# LVBMSBQF_schematic.net
KiCad netlist of a schematic drawn in Altium Designer
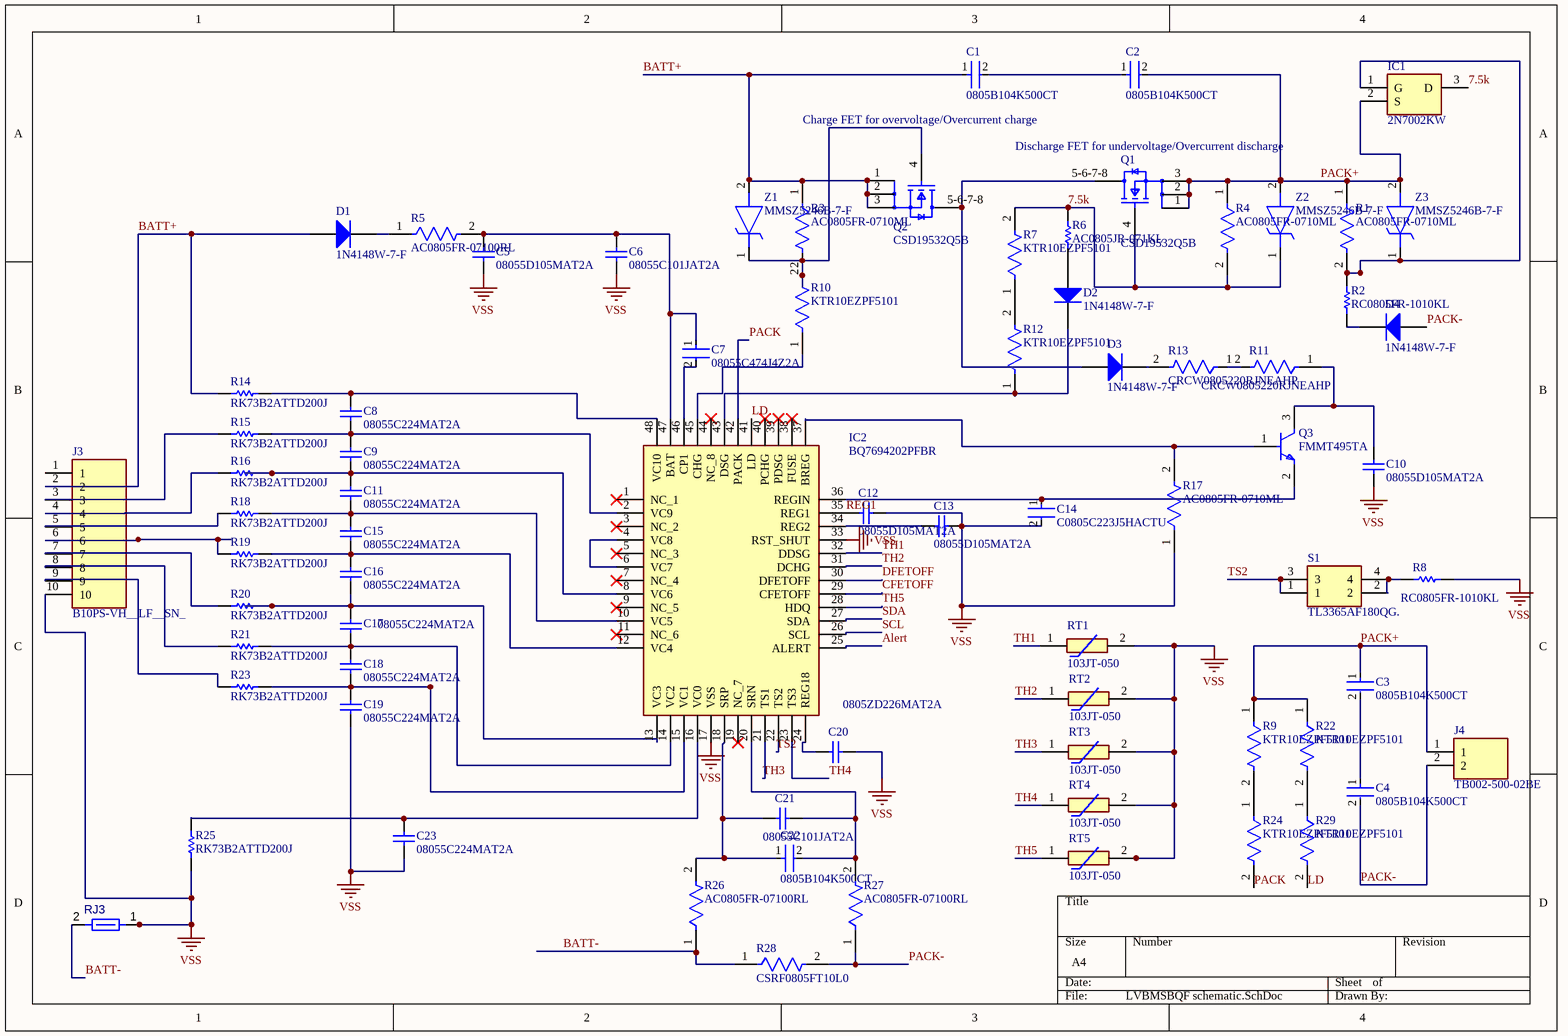
[diagram p0: LVBMSBQF schematic.SchDoc]

(export (version "E")
  (design (tool "Eeschema 10.0.6"))
  (components
    (comp (ref "C1")
      (value "0805B104K500CT")
      (footprint "FP-0805B-IPC_C")
      (description "CAP CER 0.1UF 50V X7R 0805")
      (fields (field (name "VOLTAGE") "50V") (field (name "TOLERANCE") "10%"))
      (libsource (lib "Altium Content Vault") (part "02cd4be3c70576c341d710602a673aa"))
    )
    (comp (ref "C2")
      (value "0805B104K500CT")
      (footprint "FP-0805B-IPC_C")
      (description "CAP CER 0.1UF 50V X7R 0805")
      (fields (field (name "VOLTAGE") "50V") (field (name "TOLERANCE") "10%"))
      (libsource (lib "Altium Content Vault") (part "02cd4be3c70576c341d710602a673aa"))
    )
    (comp (ref "C3")
      (value "0805B104K500CT")
      (footprint "FP-0805B-IPC_C")
      (description "CAP CER 0.1UF 50V X7R 0805")
      (fields (field (name "VOLTAGE") "50V") (field (name "TOLERANCE") "10%"))
      (libsource (lib "Altium Content Vault") (part "02cd4be3c70576c341d710602a673aa"))
    )
    (comp (ref "C4")
      (value "0805B104K500CT")
      (footprint "FP-0805B-IPC_C")
      (description "CAP CER 0.1UF 50V X7R 0805")
      (fields (field (name "VOLTAGE") "50V") (field (name "TOLERANCE") "10%"))
      (libsource (lib "Altium Content Vault") (part "02cd4be3c70576c341d710602a673aa"))
    )
    (comp (ref "C5")
      (value "08055D105MAT2A")
      (footprint "CAPC2013X152X50ML20T25")
      (libsource (lib "Altium Content Vault") (part "CAP"))
    )
    (comp (ref "C6")
      (value "08055C101JAT2A")
      (footprint "CAPC2013X94X50NL20T25")
      (libsource (lib "Altium Content Vault") (part "CAP"))
    )
    (comp (ref "C7")
      (value "08055C474J4Z2A")
      (footprint "FP-0805-L_2_01_0_2-W_1_25-IPC_B")
      (description "Automotive Ceramic Capacitor, 0805, 470nF, 5%, X7R, 15%, 50V")
      (fields (field (name "TOLERANCE") "5%"))
      (libsource (lib "Altium Content Vault") (part "b4654b650e69147ec39a6b967a45e02"))
    )
    (comp (ref "C8")
      (value "08055C224MAT2A")
      (footprint "CAPC2013X140X50NL20T25")
      (libsource (lib "Altium Content Vault") (part "CAP"))
    )
    (comp (ref "C9")
      (value "08055C224MAT2A")
      (footprint "CAPC2013X140X50NL20T25")
      (libsource (lib "Altium Content Vault") (part "CAP"))
    )
    (comp (ref "C10")
      (value "08055D105MAT2A")
      (footprint "CAPC2013X152X50ML20T25")
      (libsource (lib "Altium Content Vault") (part "CAP"))
    )
    (comp (ref "C11")
      (value "08055C224MAT2A")
      (footprint "CAPC2013X140X50NL20T25")
      (libsource (lib "Altium Content Vault") (part "CAP"))
    )
    (comp (ref "C12")
      (value "08055D105MAT2A")
      (footprint "CAPC2013X152X50ML20T25")
      (libsource (lib "Altium Content Vault") (part "CAP"))
    )
    (comp (ref "C13")
      (value "08055D105MAT2A")
      (footprint "CAPC2013X152X50ML20T25")
      (libsource (lib "Altium Content Vault") (part "CAP"))
    )
    (comp (ref "C14")
      (value "C0805C223J5HACTU")
      (footprint "FP-C0805C-DN-MFG")
      (description "CAP CER 0.022UF 50V X8R 0805")
      (fields
        (field (name "TOLERANCE") "0.05")
        (field (name "OCTOPART") "https://octopart.com/c0805c223j5hactu-kemet-18638969")
      )
      (libsource (lib "Altium Content Vault") (part "b4654b650e69147ec39a6b967a45e02"))
    )
    (comp (ref "C15")
      (value "08055C224MAT2A")
      (footprint "CAPC2013X140X50NL20T25")
      (libsource (lib "Altium Content Vault") (part "CAP"))
    )
    (comp (ref "C16")
      (value "08055C224MAT2A")
      (footprint "CAPC2013X140X50NL20T25")
      (libsource (lib "Altium Content Vault") (part "CAP"))
    )
    (comp (ref "C17")
      (value "08055C224MAT2A")
      (footprint "CAPC2013X140X50NL20T25")
      (libsource (lib "Altium Content Vault") (part "CAP"))
    )
    (comp (ref "C18")
      (value "08055C224MAT2A")
      (footprint "CAPC2013X140X50NL20T25")
      (libsource (lib "Altium Content Vault") (part "CAP"))
    )
    (comp (ref "C19")
      (value "08055C224MAT2A")
      (footprint "CAPC2013X140X50NL20T25")
      (libsource (lib "Altium Content Vault") (part "CAP"))
    )
    (comp (ref "C20")
      (value "0805ZD226MAT2A")
      (footprint "CAPC2013X152X50ML20T25")
      (libsource (lib "Altium Content Vault") (part "CAP"))
    )
    (comp (ref "C21")
      (value "08055C101JAT2A")
      (footprint "CAPC2013X94X50NL20T25")
      (libsource (lib "Altium Content Vault") (part "CAP"))
    )
    (comp (ref "C22")
      (value "0805B104K500CT")
      (footprint "FP-0805B-IPC_C")
      (description "CAP CER 0.1UF 50V X7R 0805")
      (fields (field (name "VOLTAGE") "50V") (field (name "TOLERANCE") "10%"))
      (libsource (lib "Altium Content Vault") (part "02cd4be3c70576c341d710602a673aa"))
    )
    (comp (ref "C23")
      (value "08055C224MAT2A")
      (footprint "CAPC2013X140X50NL20T25")
      (libsource (lib "Altium Content Vault") (part "CAP"))
    )
    (comp (ref "D1")
      (value "1N4148W-7-F")
      (footprint "DIOD-SOD123-2_V")
      (description "Fast Switching Diode, 100 V, 0.15 A, -65 to 150 degC, 2-Pin?SOD123, RoHS, Tape and Reel")
      (libsource (lib "Altium Content Vault") (part "D-AK-2"))
    )
    (comp (ref "D2")
      (value "1N4148W-7-F")
      (footprint "DIOD-SOD123-2_V")
      (description "Fast Switching Diode, 100 V, 0.15 A, -65 to 150 degC, 2-Pin?SOD123, RoHS, Tape and Reel")
      (libsource (lib "Altium Content Vault") (part "D-AK-2"))
    )
    (comp (ref "D3")
      (value "1N4148W-7-F")
      (footprint "DIOD-SOD123-2_V")
      (description "Fast Switching Diode, 100 V, 0.15 A, -65 to 150 degC, 2-Pin?SOD123, RoHS, Tape and Reel")
      (libsource (lib "Altium Content Vault") (part "D-AK-2"))
    )
    (comp (ref "D4")
      (value "1N4148W-7-F")
      (footprint "DIOD-SOD123-2_V")
      (description "Fast Switching Diode, 100 V, 0.15 A, -65 to 150 degC, 2-Pin?SOD123, RoHS, Tape and Reel")
      (fields (field (name "MANUFACTURER") "DiodesIncorporated"))
      (libsource (lib "Altium Content Vault") (part "D-AK-2"))
    )
    (comp (ref "IC1")
      (value "2N7002KW")
      (footprint "SamacSys:SOT65P210X110-3N")
      (description "Integrated Circuit")
      (fields (field (name "MOUSER PART NUMBER") "512-2N7002KW"))
      (libsource (lib "*") (part "2N7002KW"))
    )
    (comp (ref "IC2")
      (value "BQ7694202PFBR")
      (footprint "SamacSys:QFP50P900X900X120-48N")
      (description "Integrated Circuit")
      (fields (field (name "MOUSER PART NUMBER") "595-BQ7694202PFBR"))
      (libsource (lib "*") (part "BQ7694202PFBR"))
    )
    (comp (ref "J3")
      (value "B10PS-VH__LF__SN_")
      (footprint "SamacSys:B10PSVHLFSN")
      (description "Connector")
      (fields (field (name "MANUFACTURER_PART_NUMBER") "B10PS-VH (LF)(SN)"))
      (libsource (lib "*") (part "B10PS-VH__LF__SN_"))
    )
    (comp (ref "J4")
      (value "TB002-500-02BE")
      (footprint "SamacSys:TB00250002BE")
      (description "Connector")
      (fields (field (name "MOUSER PART NUMBER") "490-TB002-500-02BE"))
      (libsource (lib "*") (part "TB002-500-02BE"))
    )
    (comp (ref "Q1")
      (value "CSD19532Q5B")
      (footprint "FP-DNK0008A-MFG")
      (description "MOSFET N-CH 100V 100A 8SON")
      (fields (field (name "OCTOPART") "https://octopart.com/csd19532q5b-texas+instruments-32890191"))
      (libsource (lib "Altium Content Vault") (part "6fb2c024a3b9031f6d89538bc87a0fd"))
    )
    (comp (ref "Q2")
      (value "CSD19532Q5B")
      (footprint "FP-DNK0008A-MFG")
      (description "MOSFET N-CH 100V 100A 8SON")
      (fields (field (name "OCTOPART") "https://octopart.com/csd19532q5b-texas+instruments-32890191"))
      (libsource (lib "Altium Content Vault") (part "6fb2c024a3b9031f6d89538bc87a0fd"))
    )
    (comp (ref "Q3")
      (value "FMMT495TA")
      (footprint "FP-SOT23-MFG")
      (description "TRANS NPN 150V 1A SOT23-3")
      (fields (field (name "OCTOPART") "https://octopart.com/fmmt495ta-diodes+inc.-356348"))
      (libsource (lib "Altium Content Vault") (part "b44e953556f554d0102664c7d152cb4"))
    )
    (comp (ref "R1")
      (value "AC0805FR-0710ML")
      (footprint "FP-AC0805-MFG")
      (description "RES SMD 10M OHM 1% 1/8W 0805")
      (fields
        (field (name "TOLERANCE") "0.01")
        (field (name "OCTOPART") "https://octopart.com/ac0805fr-0710ml-yageo-71367525")
      )
      (libsource (lib "Altium Content Vault") (part "1029c3af85768c4190bb7ad29bc67b5"))
    )
    (comp (ref "R2")
      (value "RC0805FR-1010KL")
      (footprint "RESC2013X60X35LL10T20")
      (libsource (lib "Altium Content Vault") (part "RES"))
    )
    (comp (ref "R3")
      (value "AC0805FR-0710ML")
      (footprint "FP-AC0805-MFG")
      (description "RES SMD 10M OHM 1% 1/8W 0805")
      (fields
        (field (name "TOLERANCE") "0.01")
        (field (name "OCTOPART") "https://octopart.com/ac0805fr-0710ml-yageo-71367525")
      )
      (libsource (lib "Altium Content Vault") (part "1029c3af85768c4190bb7ad29bc67b5"))
    )
    (comp (ref "R4")
      (value "AC0805FR-0710ML")
      (footprint "FP-AC0805-MFG")
      (description "RES SMD 10M OHM 1% 1/8W 0805")
      (fields
        (field (name "TOLERANCE") "0.01")
        (field (name "OCTOPART") "https://octopart.com/ac0805fr-0710ml-yageo-71367525")
      )
      (libsource (lib "Altium Content Vault") (part "1029c3af85768c4190bb7ad29bc67b5"))
    )
    (comp (ref "R5")
      (value "AC0805FR-07100RL")
      (footprint "FP-AC0805-MFG")
      (description "Res Thick Film 0805 100 Ohm 1% 1/8W ±100ppm/°C Molded SMD Paper T/R")
      (fields
        (field (name "TOLERANCE") "0.01")
        (field (name "OCTOPART") "https://octopart.com/ac0805fr-07100rl-yageo-24517276")
      )
      (libsource (lib "Altium Content Vault") (part "1029c3af85768c4190bb7ad29bc67b5"))
    )
    (comp (ref "R6")
      (value "AC0805JR-071KL")
      (footprint "RESC2013X60X35LL10T20")
      (libsource (lib "Altium Content Vault") (part "RES"))
    )
    (comp (ref "R7")
      (value "KTR10EZPF5101")
      (footprint "FP-KTR10-MFG")
      (description "Res Thick Film 0805 5.1kΩ 1% 0.125W ±100ppm/°C Automotive Paper T/R")
      (fields (field (name "TOLERANCE") "1%"))
      (libsource (lib "Altium Content Vault") (part "1029c3af85768c4190bb7ad29bc67b5"))
    )
    (comp (ref "R8")
      (value "RC0805FR-1010KL")
      (footprint "RESC2013X60X35LL10T20")
      (libsource (lib "Altium Content Vault") (part "RES"))
    )
    (comp (ref "R9")
      (value "KTR10EZPF5101")
      (footprint "FP-KTR10-MFG")
      (description "Res Thick Film 0805 5.1kΩ 1% 0.125W ±100ppm/°C Automotive Paper T/R")
      (fields (field (name "TOLERANCE") "1%"))
      (libsource (lib "Altium Content Vault") (part "1029c3af85768c4190bb7ad29bc67b5"))
    )
    (comp (ref "R10")
      (value "KTR10EZPF5101")
      (footprint "FP-KTR10-MFG")
      (description "Res Thick Film 0805 5.1kΩ 1% 0.125W ±100ppm/°C Automotive Paper T/R")
      (fields (field (name "TOLERANCE") "1%"))
      (libsource (lib "Altium Content Vault") (part "1029c3af85768c4190bb7ad29bc67b5"))
    )
    (comp (ref "R11")
      (value "CRCW0805220RJNEAHP")
      (footprint "FP-CRCW0805-HPe3-IPC_A")
      (description "RES Thick Film, 220Ω, 5%, 0.5W, 200ppm/°C, 0805")
      (fields (field (name "TOLERANCE") "5%"))
      (libsource (lib "Altium Content Vault") (part "1029c3af85768c4190bb7ad29bc67b5"))
    )
    (comp (ref "R12")
      (value "KTR10EZPF5101")
      (footprint "FP-KTR10-MFG")
      (description "Res Thick Film 0805 5.1kΩ 1% 0.125W ±100ppm/°C Automotive Paper T/R")
      (fields (field (name "TOLERANCE") "1%"))
      (libsource (lib "Altium Content Vault") (part "1029c3af85768c4190bb7ad29bc67b5"))
    )
    (comp (ref "R13")
      (value "CRCW0805220RJNEAHP")
      (footprint "FP-CRCW0805-HPe3-IPC_A")
      (description "RES Thick Film, 220Ω, 5%, 0.5W, 200ppm/°C, 0805")
      (fields (field (name "TOLERANCE") "5%"))
      (libsource (lib "Altium Content Vault") (part "1029c3af85768c4190bb7ad29bc67b5"))
    )
    (comp (ref "R14")
      (value "RK73B2ATTD200J")
      (footprint "RESC2013X60X30ML20T20")
      (libsource (lib "Altium Content Vault") (part "RES"))
    )
    (comp (ref "R15")
      (value "RK73B2ATTD200J")
      (footprint "RESC2013X60X30ML20T20")
      (libsource (lib "Altium Content Vault") (part "RES"))
    )
    (comp (ref "R16")
      (value "RK73B2ATTD200J")
      (footprint "RESC2013X60X30ML20T20")
      (libsource (lib "Altium Content Vault") (part "RES"))
    )
    (comp (ref "R17")
      (value "AC0805FR-0710ML")
      (footprint "FP-AC0805-MFG")
      (description "RES SMD 10M OHM 1% 1/8W 0805")
      (fields
        (field (name "TOLERANCE") "0.01")
        (field (name "OCTOPART") "https://octopart.com/ac0805fr-0710ml-yageo-71367525")
      )
      (libsource (lib "Altium Content Vault") (part "1029c3af85768c4190bb7ad29bc67b5"))
    )
    (comp (ref "R18")
      (value "RK73B2ATTD200J")
      (footprint "RESC2013X60X30ML20T20")
      (libsource (lib "Altium Content Vault") (part "RES"))
    )
    (comp (ref "R19")
      (value "RK73B2ATTD200J")
      (footprint "RESC2013X60X30ML20T20")
      (libsource (lib "Altium Content Vault") (part "RES"))
    )
    (comp (ref "R20")
      (value "RK73B2ATTD200J")
      (footprint "RESC2013X60X30ML20T20")
      (libsource (lib "Altium Content Vault") (part "RES"))
    )
    (comp (ref "R21")
      (value "RK73B2ATTD200J")
      (footprint "RESC2013X60X30ML20T20")
      (libsource (lib "Altium Content Vault") (part "RES"))
    )
    (comp (ref "R22")
      (value "KTR10EZPF5101")
      (footprint "FP-KTR10-MFG")
      (description "Res Thick Film 0805 5.1kΩ 1% 0.125W ±100ppm/°C Automotive Paper T/R")
      (fields (field (name "TOLERANCE") "1%"))
      (libsource (lib "Altium Content Vault") (part "1029c3af85768c4190bb7ad29bc67b5"))
    )
    (comp (ref "R23")
      (value "RK73B2ATTD200J")
      (footprint "RESC2013X60X30ML20T20")
      (libsource (lib "Altium Content Vault") (part "RES"))
    )
    (comp (ref "R24")
      (value "KTR10EZPF5101")
      (footprint "FP-KTR10-MFG")
      (description "Res Thick Film 0805 5.1kΩ 1% 0.125W ±100ppm/°C Automotive Paper T/R")
      (fields (field (name "TOLERANCE") "1%"))
      (libsource (lib "Altium Content Vault") (part "1029c3af85768c4190bb7ad29bc67b5"))
    )
    (comp (ref "R25")
      (value "RK73B2ATTD200J")
      (footprint "RESC2013X60X30ML20T20")
      (libsource (lib "Altium Content Vault") (part "RES"))
    )
    (comp (ref "R26")
      (value "AC0805FR-07100RL")
      (footprint "FP-AC0805-MFG")
      (description "Res Thick Film 0805 100 Ohm 1% 1/8W ±100ppm/°C Molded SMD Paper T/R")
      (fields
        (field (name "TOLERANCE") "0.01")
        (field (name "OCTOPART") "https://octopart.com/ac0805fr-07100rl-yageo-24517276")
      )
      (libsource (lib "Altium Content Vault") (part "1029c3af85768c4190bb7ad29bc67b5"))
    )
    (comp (ref "R27")
      (value "AC0805FR-07100RL")
      (footprint "FP-AC0805-MFG")
      (description "Res Thick Film 0805 100 Ohm 1% 1/8W ±100ppm/°C Molded SMD Paper T/R")
      (fields
        (field (name "TOLERANCE") "0.01")
        (field (name "OCTOPART") "https://octopart.com/ac0805fr-07100rl-yageo-24517276")
      )
      (libsource (lib "Altium Content Vault") (part "1029c3af85768c4190bb7ad29bc67b5"))
    )
    (comp (ref "R28")
      (value "CSRF0805FT10L0")
      (footprint "FP-CSRF0805-IPC_A")
      (description "Foil on Ceramic Current Sensing Chip Resistor 10 mΩ ±1% 0.5W 0805 AEC Qualified")
      (fields (field (name "TOLERANCE") "1%"))
      (libsource (lib "Altium Content Vault") (part "1029c3af85768c4190bb7ad29bc67b5"))
    )
    (comp (ref "R29")
      (value "KTR10EZPF5101")
      (footprint "FP-KTR10-MFG")
      (description "Res Thick Film 0805 5.1kΩ 1% 0.125W ±100ppm/°C Automotive Paper T/R")
      (fields (field (name "TOLERANCE") "1%"))
      (libsource (lib "Altium Content Vault") (part "1029c3af85768c4190bb7ad29bc67b5"))
    )
    (comp (ref "RJ3")
      (value "Net Tie 0.6x1.4mm")
      (footprint "SHORT10_8MIL-FP")
      (libsource (lib "Toronto Met Formula Racing") (part "CMP-00022-00002-2"))
    )
    (comp (ref "RT1")
      (value "103JT-050")
      (footprint "SamacSys:103JT050")
      (description "Thermistor")
      (fields (field (name "MOUSER PART NUMBER") "954-103JT-050"))
      (libsource (lib "*") (part "103JT-050"))
    )
    (comp (ref "RT2")
      (value "103JT-050")
      (footprint "SamacSys:103JT050")
      (description "Thermistor")
      (fields (field (name "MOUSER PART NUMBER") "954-103JT-050"))
      (libsource (lib "*") (part "103JT-050"))
    )
    (comp (ref "RT3")
      (value "103JT-050")
      (footprint "SamacSys:103JT050")
      (description "Thermistor")
      (fields (field (name "MOUSER PART NUMBER") "954-103JT-050"))
      (libsource (lib "*") (part "103JT-050"))
    )
    (comp (ref "RT4")
      (value "103JT-050")
      (footprint "SamacSys:103JT050")
      (description "Thermistor")
      (fields (field (name "MOUSER PART NUMBER") "954-103JT-050"))
      (libsource (lib "*") (part "103JT-050"))
    )
    (comp (ref "RT5")
      (value "103JT-050")
      (footprint "SamacSys:103JT050")
      (description "Thermistor")
      (fields (field (name "MOUSER PART NUMBER") "954-103JT-050"))
      (libsource (lib "*") (part "103JT-050"))
    )
    (comp (ref "S1")
      (value "TL3365AF180QG.")
      (footprint "SamacSys:TL3365AF180QG")
      (description "Switch")
      (libsource (lib "*") (part "TL3365AF180QG."))
    )
    (comp (ref "Z1")
      (value "MMSZ5246B-7-F")
      (footprint "SamacSys:SOD3716X145N")
      (description "Zener Diode")
      (fields (field (name "MOUSER PART NUMBER") "621-MMSZ5246B-F"))
      (libsource (lib "*") (part "MMSZ5246B-7-F"))
    )
    (comp (ref "Z2")
      (value "MMSZ5246B-7-F")
      (footprint "SamacSys:SOD3716X145N")
      (description "Zener Diode")
      (fields (field (name "MOUSER PART NUMBER") "621-MMSZ5246B-F"))
      (libsource (lib "*") (part "MMSZ5246B-7-F"))
    )
    (comp (ref "Z3")
      (value "MMSZ5246B-7-F")
      (footprint "SamacSys:SOD3716X145N")
      (description "Zener Diode")
      (fields (field (name "MOUSER PART NUMBER") "621-MMSZ5246B-F"))
      (libsource (lib "*") (part "MMSZ5246B-7-F"))
    )
  )
  (nets
    (net (code "1") (name "/7.5k") (class "Default")
      (node (ref "IC1") (pin "3") (pinfunction "D_3") (pintype "passive"))
      (node (ref "Q1") (pin "4") (pinfunction "G_4") (pintype "passive"))
      (node (ref "R4") (pin "2") (pinfunction "2_2") (pintype "passive"))
      (node (ref "R6") (pin "2") (pinfunction "2_2") (pintype "passive"))
      (node (ref "R7") (pin "2") (pinfunction "2_2") (pintype "passive"))
      (node (ref "Z2") (pin "1") (pinfunction "K_1") (pintype "passive"))
    )
    (net (code "2") (name "/Alert") (class "Default")
      (node (ref "IC2") (pin "25") (pinfunction "ALERT_25") (pintype "passive"))
    )
    (net (code "3") (name "/BATT+") (class "Default")
      (node (ref "C1") (pin "1") (pinfunction "1_1") (pintype "passive"))
      (node (ref "D1") (pin "1") (pinfunction "A_1") (pintype "passive"))
      (node (ref "J3") (pin "2") (pinfunction "2_2") (pintype "passive"))
      (node (ref "Q2") (pin "1") (pinfunction "S_1") (pintype "passive"))
      (node (ref "Q2") (pin "2") (pinfunction "S_2") (pintype "passive"))
      (node (ref "Q2") (pin "3") (pinfunction "S_3") (pintype "passive"))
      (node (ref "R14") (pin "1") (pinfunction "1_1") (pintype "passive"))
      (node (ref "R3") (pin "1") (pinfunction "1_1") (pintype "passive"))
      (node (ref "Z1") (pin "2") (pinfunction "A_2") (pintype "passive"))
    )
    (net (code "4") (name "/BATT-") (class "Default")
      (node (ref "R26") (pin "1") (pinfunction "1_1") (pintype "passive"))
      (node (ref "R28") (pin "1") (pinfunction "1_1") (pintype "passive"))
      (node (ref "RJ3") (pin "2") (pinfunction "2_2") (pintype "passive"))
    )
    (net (code "5") (name "/CFETOFF") (class "Default")
      (node (ref "IC2") (pin "29") (pinfunction "CFETOFF_29") (pintype "passive"))
    )
    (net (code "6") (name "/DFETOFF") (class "Default")
      (node (ref "IC2") (pin "30") (pinfunction "DFETOFF_30") (pintype "passive"))
    )
    (net (code "7") (name "/LD") (class "Default")
      (node (ref "IC2") (pin "41") (pinfunction "LD_41") (pintype "passive"))
      (node (ref "R29") (pin "2") (pinfunction "2_2") (pintype "passive"))
    )
    (net (code "8") (name "/PACK") (class "Default")
      (node (ref "IC2") (pin "42") (pinfunction "PACK_42") (pintype "passive"))
      (node (ref "R24") (pin "2") (pinfunction "2_2") (pintype "passive"))
    )
    (net (code "9") (name "/PACK+") (class "Default")
      (node (ref "C2") (pin "2") (pinfunction "2_2") (pintype "passive"))
      (node (ref "C3") (pin "1") (pinfunction "1_1") (pintype "passive"))
      (node (ref "IC1") (pin "2") (pinfunction "S_2") (pintype "passive"))
      (node (ref "J4") (pin "1") (pinfunction "1_1") (pintype "passive"))
      (node (ref "Q1") (pin "1") (pinfunction "S_1") (pintype "passive"))
      (node (ref "Q1") (pin "2") (pinfunction "S_2") (pintype "passive"))
      (node (ref "Q1") (pin "3") (pinfunction "S_3") (pintype "passive"))
      (node (ref "R1") (pin "1") (pinfunction "1_1") (pintype "passive"))
      (node (ref "R22") (pin "1") (pinfunction "1_1") (pintype "passive"))
      (node (ref "R4") (pin "1") (pinfunction "1_1") (pintype "passive"))
      (node (ref "R9") (pin "1") (pinfunction "1_1") (pintype "passive"))
      (node (ref "Z2") (pin "2") (pinfunction "A_2") (pintype "passive"))
      (node (ref "Z3") (pin "2") (pinfunction "A_2") (pintype "passive"))
    )
    (net (code "10") (name "/PACK-") (class "Default")
      (node (ref "C4") (pin "2") (pinfunction "2_2") (pintype "passive"))
      (node (ref "D4") (pin "1") (pinfunction "A_1") (pintype "passive"))
      (node (ref "J4") (pin "2") (pinfunction "2_2") (pintype "passive"))
      (node (ref "R27") (pin "1") (pinfunction "1_1") (pintype "passive"))
      (node (ref "R28") (pin "2") (pinfunction "2_2") (pintype "passive"))
    )
    (net (code "11") (name "/REG1") (class "Default")
      (node (ref "C12") (pin "1") (pinfunction "1_1") (pintype "passive"))
      (node (ref "IC2") (pin "35") (pinfunction "REG1_35") (pintype "passive"))
    )
    (net (code "12") (name "/SCL") (class "Default")
      (node (ref "IC2") (pin "26") (pinfunction "SCL_26") (pintype "passive"))
    )
    (net (code "13") (name "/SDA") (class "Default")
      (node (ref "IC2") (pin "27") (pinfunction "SDA_27") (pintype "passive"))
    )
    (net (code "14") (name "/TH1") (class "Default")
      (node (ref "IC2") (pin "32") (pinfunction "DDSG_32") (pintype "passive"))
      (node (ref "RT1") (pin "1") (pinfunction "1_1") (pintype "passive"))
    )
    (net (code "15") (name "/TH2") (class "Default")
      (node (ref "IC2") (pin "31") (pinfunction "DCHG_31") (pintype "passive"))
      (node (ref "RT2") (pin "1") (pinfunction "1_1") (pintype "passive"))
    )
    (net (code "16") (name "/TH3") (class "Default")
      (node (ref "IC2") (pin "21") (pinfunction "TS1_21") (pintype "passive"))
      (node (ref "RT3") (pin "1") (pinfunction "1_1") (pintype "passive"))
    )
    (net (code "17") (name "/TH4") (class "Default")
      (node (ref "IC2") (pin "23") (pinfunction "TS3_23") (pintype "passive"))
      (node (ref "RT4") (pin "1") (pinfunction "1_1") (pintype "passive"))
    )
    (net (code "18") (name "/TH5") (class "Default")
      (node (ref "IC2") (pin "28") (pinfunction "HDQ_28") (pintype "passive"))
      (node (ref "RT5") (pin "1") (pinfunction "1_1") (pintype "passive"))
    )
    (net (code "19") (name "/TS2") (class "Default")
      (node (ref "IC2") (pin "22") (pinfunction "TS2_22") (pintype "passive"))
      (node (ref "S1") (pin "1") (pinfunction "1_1") (pintype "passive"))
      (node (ref "S1") (pin "3") (pinfunction "3_3") (pintype "passive"))
    )
    (net (code "20") (name "Net-(C1-Pad2)") (class "Default")
      (node (ref "C1") (pin "2") (pinfunction "2_2") (pintype "passive"))
      (node (ref "C2") (pin "1") (pinfunction "1_1") (pintype "passive"))
    )
    (net (code "21") (name "Net-(C3-Pad2)") (class "Default")
      (node (ref "C3") (pin "2") (pinfunction "2_2") (pintype "passive"))
      (node (ref "C4") (pin "1") (pinfunction "1_1") (pintype "passive"))
    )
    (net (code "22") (name "Net-(D1-K)") (class "Default")
      (node (ref "D1") (pin "2") (pinfunction "K_2") (pintype "passive"))
      (node (ref "R5") (pin "1") (pinfunction "1_1") (pintype "passive"))
    )
    (net (code "23") (name "Net-(D2-A)") (class "Default")
      (node (ref "D2") (pin "1") (pinfunction "A_1") (pintype "passive"))
      (node (ref "R6") (pin "1") (pinfunction "1_1") (pintype "passive"))
    )
    (net (code "24") (name "Net-(D2-K)") (class "Default")
      (node (ref "D2") (pin "2") (pinfunction "K_2") (pintype "passive"))
      (node (ref "IC2") (pin "43") (pinfunction "DSG_43") (pintype "passive"))
      (node (ref "R12") (pin "1") (pinfunction "1_1") (pintype "passive"))
    )
    (net (code "25") (name "Net-(D3-A)") (class "Default")
      (node (ref "D3") (pin "1") (pinfunction "A_1") (pintype "passive"))
      (node (ref "Q1") (pin "5-6-7-8") (pinfunction "D_5-6-7-8") (pintype "passive"))
      (node (ref "Q2") (pin "5-6-7-8") (pinfunction "D_5-6-7-8") (pintype "passive"))
    )
    (net (code "26") (name "Net-(D3-K)") (class "Default")
      (node (ref "D3") (pin "2") (pinfunction "K_2") (pintype "passive"))
      (node (ref "R13") (pin "2") (pinfunction "2_2") (pintype "passive"))
    )
    (net (code "27") (name "Net-(D4-K)") (class "Default")
      (node (ref "D4") (pin "2") (pinfunction "K_2") (pintype "passive"))
      (node (ref "R2") (pin "2") (pinfunction "2_2") (pintype "passive"))
    )
    (net (code "28") (name "Net-(IC1-G)") (class "Default")
      (node (ref "IC1") (pin "1") (pinfunction "G_1") (pintype "passive"))
      (node (ref "R1") (pin "2") (pinfunction "2_2") (pintype "passive"))
      (node (ref "R2") (pin "1") (pinfunction "1_1") (pintype "passive"))
      (node (ref "Z3") (pin "1") (pinfunction "K_1") (pintype "passive"))
    )
    (net (code "29") (name "Net-(IC2-BAT)") (class "Default")
      (node (ref "C5") (pin "2") (pinfunction "2_2") (pintype "passive"))
      (node (ref "C6") (pin "2") (pinfunction "2_2") (pintype "passive"))
      (node (ref "C7") (pin "1") (pinfunction "1_1") (pintype "passive"))
      (node (ref "IC2") (pin "47") (pinfunction "BAT_47") (pintype "passive"))
      (node (ref "R5") (pin "2") (pinfunction "2_2") (pintype "passive"))
    )
    (net (code "30") (name "Net-(IC2-BREG)") (class "Default")
      (node (ref "IC2") (pin "37") (pinfunction "BREG_37") (pintype "passive"))
      (node (ref "Q3") (pin "1") (pinfunction "B_1") (pintype "passive"))
      (node (ref "R17") (pin "2") (pinfunction "2_2") (pintype "passive"))
    )
    (net (code "31") (name "Net-(IC2-CHG)") (class "Default")
      (node (ref "IC2") (pin "45") (pinfunction "CHG_45") (pintype "passive"))
      (node (ref "R10") (pin "1") (pinfunction "1_1") (pintype "passive"))
    )
    (net (code "32") (name "Net-(IC2-CP1)") (class "Default")
      (node (ref "C7") (pin "2") (pinfunction "2_2") (pintype "passive"))
      (node (ref "IC2") (pin "46") (pinfunction "CP1_46") (pintype "passive"))
    )
    (net (code "33") (name "Net-(IC2-REG2)") (class "Default")
      (node (ref "C13") (pin "1") (pinfunction "1_1") (pintype "passive"))
      (node (ref "IC2") (pin "34") (pinfunction "REG2_34") (pintype "passive"))
    )
    (net (code "34") (name "Net-(IC2-REG18)") (class "Default")
      (node (ref "C20") (pin "1") (pinfunction "1_1") (pintype "passive"))
      (node (ref "IC2") (pin "24") (pinfunction "REG18_24") (pintype "passive"))
    )
    (net (code "35") (name "Net-(IC2-REGIN)") (class "Default")
      (node (ref "C14") (pin "1") (pinfunction "1_1") (pintype "passive"))
      (node (ref "IC2") (pin "36") (pinfunction "REGIN_36") (pintype "passive"))
      (node (ref "Q3") (pin "2") (pinfunction "E_2") (pintype "passive"))
    )
    (net (code "36") (name "Net-(IC2-SRN)") (class "Default")
      (node (ref "C21") (pin "1") (pinfunction "1_1") (pintype "passive"))
      (node (ref "C22") (pin "2") (pinfunction "2_2") (pintype "passive"))
      (node (ref "IC2") (pin "20") (pinfunction "SRN_20") (pintype "passive"))
      (node (ref "R27") (pin "2") (pinfunction "2_2") (pintype "passive"))
    )
    (net (code "37") (name "Net-(IC2-SRP)") (class "Default")
      (node (ref "C21") (pin "2") (pinfunction "2_2") (pintype "passive"))
      (node (ref "C22") (pin "1") (pinfunction "1_1") (pintype "passive"))
      (node (ref "IC2") (pin "18") (pinfunction "SRP_18") (pintype "passive"))
      (node (ref "R26") (pin "2") (pinfunction "2_2") (pintype "passive"))
    )
    (net (code "38") (name "Net-(IC2-VC0)") (class "Default")
      (node (ref "C23") (pin "2") (pinfunction "2_2") (pintype "passive"))
      (node (ref "IC2") (pin "16") (pinfunction "VC0_16") (pintype "passive"))
      (node (ref "R25") (pin "2") (pinfunction "2_2") (pintype "passive"))
    )
    (net (code "39") (name "Net-(IC2-VC1)") (class "Default")
      (node (ref "C18") (pin "1") (pinfunction "1_1") (pintype "passive"))
      (node (ref "C19") (pin "2") (pinfunction "2_2") (pintype "passive"))
      (node (ref "IC2") (pin "15") (pinfunction "VC1_15") (pintype "passive"))
      (node (ref "R23") (pin "2") (pinfunction "2_2") (pintype "passive"))
    )
    (net (code "40") (name "Net-(IC2-VC2)") (class "Default")
      (node (ref "C17") (pin "1") (pinfunction "1_1") (pintype "passive"))
      (node (ref "C18") (pin "2") (pinfunction "2_2") (pintype "passive"))
      (node (ref "IC2") (pin "14") (pinfunction "VC2_14") (pintype "passive"))
      (node (ref "R21") (pin "2") (pinfunction "2_2") (pintype "passive"))
    )
    (net (code "41") (name "Net-(IC2-VC3)") (class "Default")
      (node (ref "C16") (pin "1") (pinfunction "1_1") (pintype "passive"))
      (node (ref "C17") (pin "2") (pinfunction "2_2") (pintype "passive"))
      (node (ref "IC2") (pin "13") (pinfunction "VC3_13") (pintype "passive"))
      (node (ref "R20") (pin "2") (pinfunction "2_2") (pintype "passive"))
    )
    (net (code "42") (name "Net-(IC2-VC4)") (class "Default")
      (node (ref "C15") (pin "1") (pinfunction "1_1") (pintype "passive"))
      (node (ref "C16") (pin "2") (pinfunction "2_2") (pintype "passive"))
      (node (ref "IC2") (pin "12") (pinfunction "VC4_12") (pintype "passive"))
      (node (ref "R19") (pin "2") (pinfunction "2_2") (pintype "passive"))
    )
    (net (code "43") (name "Net-(IC2-VC5)") (class "Default")
      (node (ref "C11") (pin "1") (pinfunction "1_1") (pintype "passive"))
      (node (ref "C15") (pin "2") (pinfunction "2_2") (pintype "passive"))
      (node (ref "IC2") (pin "10") (pinfunction "VC5_10") (pintype "passive"))
      (node (ref "R18") (pin "2") (pinfunction "2_2") (pintype "passive"))
    )
    (net (code "44") (name "Net-(IC2-VC6)") (class "Default")
      (node (ref "C11") (pin "2") (pinfunction "2_2") (pintype "passive"))
      (node (ref "IC2") (pin "8") (pinfunction "VC6_8") (pintype "passive"))
      (node (ref "R16") (pin "2") (pinfunction "2_2") (pintype "passive"))
    )
    (net (code "45") (name "Net-(IC2-VC7)") (class "Default")
      (node (ref "IC2") (pin "4") (pinfunction "VC8_4") (pintype "passive"))
      (node (ref "IC2") (pin "6") (pinfunction "VC7_6") (pintype "passive"))
    )
    (net (code "46") (name "Net-(IC2-VC9)") (class "Default")
      (node (ref "C8") (pin "1") (pinfunction "1_1") (pintype "passive"))
      (node (ref "C9") (pin "2") (pinfunction "2_2") (pintype "passive"))
      (node (ref "IC2") (pin "2") (pinfunction "VC9_2") (pintype "passive"))
      (node (ref "R15") (pin "2") (pinfunction "2_2") (pintype "passive"))
    )
    (net (code "47") (name "Net-(IC2-VC10)") (class "Default")
      (node (ref "C8") (pin "2") (pinfunction "2_2") (pintype "passive"))
      (node (ref "IC2") (pin "48") (pinfunction "VC10_48") (pintype "passive"))
      (node (ref "R14") (pin "2") (pinfunction "2_2") (pintype "passive"))
    )
    (net (code "48") (name "Net-(J3-Pad3)") (class "Default")
      (node (ref "J3") (pin "3") (pinfunction "3_3") (pintype "passive"))
      (node (ref "R15") (pin "1") (pinfunction "1_1") (pintype "passive"))
    )
    (net (code "49") (name "Net-(J3-Pad4)") (class "Default")
      (node (ref "J3") (pin "4") (pinfunction "4_4") (pintype "passive"))
      (node (ref "R16") (pin "1") (pinfunction "1_1") (pintype "passive"))
    )
    (net (code "50") (name "Net-(J3-Pad5)") (class "Default")
      (node (ref "J3") (pin "5") (pinfunction "5_5") (pintype "passive"))
      (node (ref "R18") (pin "1") (pinfunction "1_1") (pintype "passive"))
    )
    (net (code "51") (name "Net-(J3-Pad6)") (class "Default")
      (node (ref "J3") (pin "6") (pinfunction "6_6") (pintype "passive"))
      (node (ref "R19") (pin "1") (pinfunction "1_1") (pintype "passive"))
    )
    (net (code "52") (name "Net-(J3-Pad7)") (class "Default")
      (node (ref "J3") (pin "7") (pinfunction "7_7") (pintype "passive"))
      (node (ref "R20") (pin "1") (pinfunction "1_1") (pintype "passive"))
    )
    (net (code "53") (name "Net-(J3-Pad8)") (class "Default")
      (node (ref "J3") (pin "8") (pinfunction "8_8") (pintype "passive"))
      (node (ref "R21") (pin "1") (pinfunction "1_1") (pintype "passive"))
    )
    (net (code "54") (name "Net-(J3-Pad9)") (class "Default")
      (node (ref "J3") (pin "9") (pinfunction "9_9") (pintype "passive"))
      (node (ref "R23") (pin "1") (pinfunction "1_1") (pintype "passive"))
    )
    (net (code "55") (name "Net-(Q2-G)") (class "Default")
      (node (ref "Q2") (pin "4") (pinfunction "G_4") (pintype "passive"))
      (node (ref "R10") (pin "2") (pinfunction "2_2") (pintype "passive"))
      (node (ref "R3") (pin "2") (pinfunction "2_2") (pintype "passive"))
      (node (ref "Z1") (pin "1") (pinfunction "K_1") (pintype "passive"))
    )
    (net (code "56") (name "Net-(Q3-C)") (class "Default")
      (node (ref "C10") (pin "2") (pinfunction "2_2") (pintype "passive"))
      (node (ref "Q3") (pin "3") (pinfunction "C_3") (pintype "passive"))
      (node (ref "R11") (pin "1") (pinfunction "1_1") (pintype "passive"))
    )
    (net (code "57") (name "Net-(R8-Pad2)") (class "Default")
      (node (ref "R8") (pin "2") (pinfunction "2_2") (pintype "passive"))
      (node (ref "S1") (pin "2") (pinfunction "2_2") (pintype "passive"))
      (node (ref "S1") (pin "4") (pinfunction "4_4") (pintype "passive"))
    )
    (net (code "58") (name "Net-(R11-Pad2)") (class "Default")
      (node (ref "R11") (pin "2") (pinfunction "2_2") (pintype "passive"))
      (node (ref "R13") (pin "1") (pinfunction "1_1") (pintype "passive"))
    )
    (net (code "59") (name "Net-(R12-Pad2)") (class "Default")
      (node (ref "R12") (pin "2") (pinfunction "2_2") (pintype "passive"))
      (node (ref "R7") (pin "1") (pinfunction "1_1") (pintype "passive"))
    )
    (net (code "60") (name "Net-(R22-Pad2)") (class "Default")
      (node (ref "R22") (pin "2") (pinfunction "2_2") (pintype "passive"))
      (node (ref "R29") (pin "1") (pinfunction "1_1") (pintype "passive"))
    )
    (net (code "61") (name "Net-(R24-Pad1)") (class "Default")
      (node (ref "R24") (pin "1") (pinfunction "1_1") (pintype "passive"))
      (node (ref "R9") (pin "2") (pinfunction "2_2") (pintype "passive"))
    )
    (net (code "62") (name "VSS") (class "Default")
      (node (ref "C10") (pin "1") (pinfunction "1_1") (pintype "passive"))
      (node (ref "C12") (pin "2") (pinfunction "2_2") (pintype "passive"))
      (node (ref "C13") (pin "2") (pinfunction "2_2") (pintype "passive"))
      (node (ref "C14") (pin "2") (pinfunction "2_2") (pintype "passive"))
      (node (ref "C19") (pin "1") (pinfunction "1_1") (pintype "passive"))
      (node (ref "C20") (pin "2") (pinfunction "2_2") (pintype "passive"))
      (node (ref "C23") (pin "1") (pinfunction "1_1") (pintype "passive"))
      (node (ref "C5") (pin "1") (pinfunction "1_1") (pintype "passive"))
      (node (ref "C6") (pin "1") (pinfunction "1_1") (pintype "passive"))
      (node (ref "IC2") (pin "17") (pinfunction "VSS_17") (pintype "passive"))
      (node (ref "IC2") (pin "33") (pinfunction "RST_SHUT_33") (pintype "passive"))
      (node (ref "J3") (pin "10") (pinfunction "10_10") (pintype "passive"))
      (node (ref "R17") (pin "1") (pinfunction "1_1") (pintype "passive"))
      (node (ref "R25") (pin "1") (pinfunction "1_1") (pintype "passive"))
      (node (ref "R8") (pin "1") (pinfunction "1_1") (pintype "passive"))
      (node (ref "RJ3") (pin "1") (pinfunction "1_1") (pintype "passive"))
      (node (ref "RT1") (pin "2") (pinfunction "2_2") (pintype "passive"))
      (node (ref "RT2") (pin "2") (pinfunction "2_2") (pintype "passive"))
      (node (ref "RT3") (pin "2") (pinfunction "2_2") (pintype "passive"))
      (node (ref "RT4") (pin "2") (pinfunction "2_2") (pintype "passive"))
      (node (ref "RT5") (pin "2") (pinfunction "2_2") (pintype "passive"))
    )
    (net (code "63") (name "unconnected-(C9-Pad1)") (class "Default")
      (node (ref "C9") (pin "1") (pinfunction "1_1") (pintype "passive"))
    )
    (net (code "64") (name "unconnected-(IC2-FUSE-Pad38)") (class "Default")
      (node (ref "IC2") (pin "38") (pinfunction "FUSE_38") (pintype "passive+no_connect"))
    )
    (net (code "65") (name "unconnected-(IC2-NC_1-Pad1)") (class "Default")
      (node (ref "IC2") (pin "1") (pinfunction "NC_1_1") (pintype "passive+no_connect"))
    )
    (net (code "66") (name "unconnected-(IC2-NC_2-Pad3)") (class "Default")
      (node (ref "IC2") (pin "3") (pinfunction "NC_2_3") (pintype "passive+no_connect"))
    )
    (net (code "67") (name "unconnected-(IC2-NC_3-Pad5)") (class "Default")
      (node (ref "IC2") (pin "5") (pinfunction "NC_3_5") (pintype "passive+no_connect"))
    )
    (net (code "68") (name "unconnected-(IC2-NC_4-Pad7)") (class "Default")
      (node (ref "IC2") (pin "7") (pinfunction "NC_4_7") (pintype "passive+no_connect"))
    )
    (net (code "69") (name "unconnected-(IC2-NC_5-Pad9)") (class "Default")
      (node (ref "IC2") (pin "9") (pinfunction "NC_5_9") (pintype "passive+no_connect"))
    )
    (net (code "70") (name "unconnected-(IC2-NC_6-Pad11)") (class "Default")
      (node (ref "IC2") (pin "11") (pinfunction "NC_6_11") (pintype "passive+no_connect"))
    )
    (net (code "71") (name "unconnected-(IC2-NC_7-Pad19)") (class "Default")
      (node (ref "IC2") (pin "19") (pinfunction "NC_7_19") (pintype "passive+no_connect"))
    )
    (net (code "72") (name "unconnected-(IC2-NC_8-Pad44)") (class "Default")
      (node (ref "IC2") (pin "44") (pinfunction "NC_8_44") (pintype "passive+no_connect"))
    )
    (net (code "73") (name "unconnected-(IC2-PCHG-Pad40)") (class "Default")
      (node (ref "IC2") (pin "40") (pinfunction "PCHG_40") (pintype "passive+no_connect"))
    )
    (net (code "74") (name "unconnected-(IC2-PDSG-Pad39)") (class "Default")
      (node (ref "IC2") (pin "39") (pinfunction "PDSG_39") (pintype "passive+no_connect"))
    )
    (net (code "75") (name "unconnected-(J3-Pad1)") (class "Default")
      (node (ref "J3") (pin "1") (pinfunction "1_1") (pintype "passive"))
    )
  )
)
